# SCH.net
KiCad netlist of a schematic drawn in Altium Designer
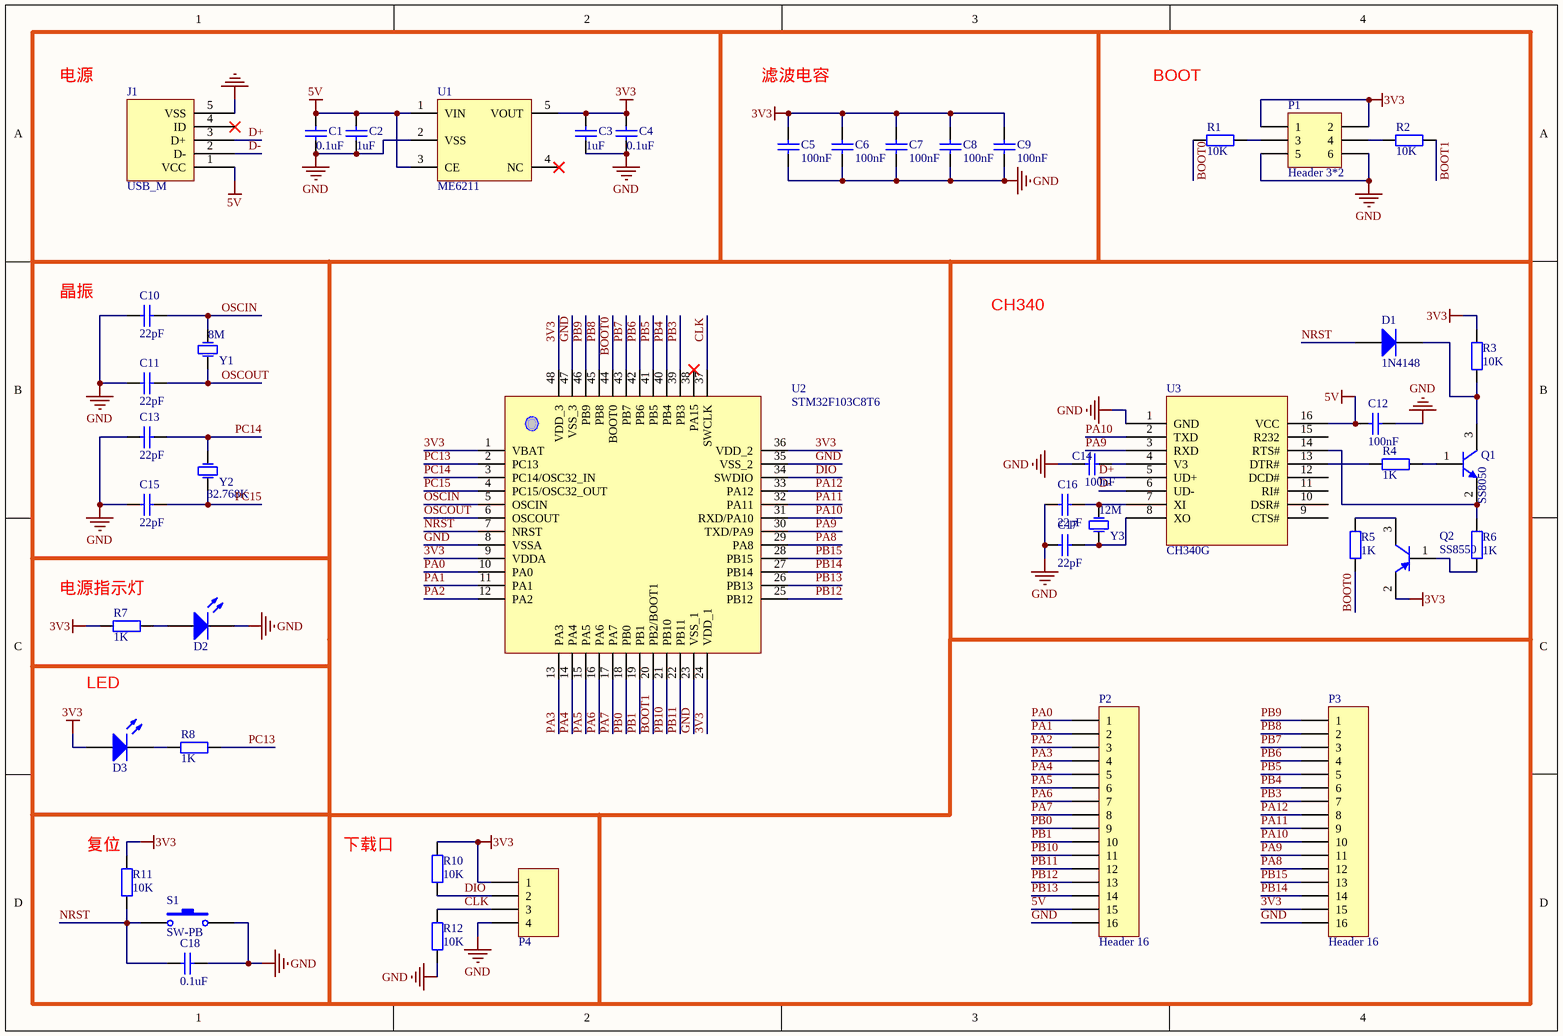
[diagram p0: SCH.SchDoc]

(export (version "E")
  (design (tool "Eeschema 10.0.6"))
  (components
    (comp (ref "C1")
      (value "0.1uF")
      (footprint "0603_C")
      (description "贴片电容")
      (fields (field (name "Comment") "Cap"))
      (libsource (lib "Miscellaneous Devices LC (1)") (part "0603 1uF (105) 10% 50V"))
    )
    (comp (ref "C2")
      (value "1uF")
      (footprint "0603_C")
      (description "贴片电容")
      (fields (field (name "Comment") "Cap"))
      (libsource (lib "Miscellaneous Devices LC (1)") (part "0603 1uF (105) 10% 50V"))
    )
    (comp (ref "C3")
      (value "1uF")
      (footprint "0603_C")
      (description "贴片电容")
      (fields (field (name "Comment") "Cap"))
      (libsource (lib "Miscellaneous Devices LC (1)") (part "0603 1uF (105) 10% 50V"))
    )
    (comp (ref "C4")
      (value "0.1uF")
      (footprint "0603_C")
      (description "贴片电容")
      (fields (field (name "Comment") "Cap"))
      (libsource (lib "Miscellaneous Devices LC (1)") (part "0603 1uF (105) 10% 50V"))
    )
    (comp (ref "C5")
      (value "100nF")
      (footprint "0603_C")
      (description "无极性电容")
      (fields (field (name "Comment") "Cap") (field (name "PUBLISHER") "Altium Limited"))
      (libsource (lib "fszhang") (part "Cap"))
    )
    (comp (ref "C6")
      (value "100nF")
      (footprint "0603_C")
      (description "无极性电容")
      (fields (field (name "Comment") "Cap") (field (name "PUBLISHER") "Altium Limited"))
      (libsource (lib "fszhang") (part "Cap"))
    )
    (comp (ref "C7")
      (value "100nF")
      (footprint "0603_C")
      (description "无极性电容")
      (fields (field (name "Comment") "Cap") (field (name "PUBLISHER") "Altium Limited"))
      (libsource (lib "fszhang") (part "Cap"))
    )
    (comp (ref "C8")
      (value "100nF")
      (footprint "0603_C")
      (description "无极性电容")
      (fields (field (name "Comment") "Cap") (field (name "PUBLISHER") "Altium Limited"))
      (libsource (lib "fszhang") (part "Cap"))
    )
    (comp (ref "C9")
      (value "100nF")
      (footprint "0603_C")
      (description "无极性电容")
      (fields (field (name "Comment") "Cap") (field (name "PUBLISHER") "Altium Limited"))
      (libsource (lib "fszhang") (part "Cap"))
    )
    (comp (ref "C10")
      (value "22pF")
      (footprint "0603_C")
      (description "无极性电容")
      (fields (field (name "Comment") "Cap") (field (name "PUBLISHER") "Altium Limited"))
      (libsource (lib "fszhang") (part "Cap"))
    )
    (comp (ref "C11")
      (value "22pF")
      (footprint "0603_C")
      (description "无极性电容")
      (fields (field (name "Comment") "Cap") (field (name "PUBLISHER") "Altium Limited"))
      (libsource (lib "fszhang") (part "Cap"))
    )
    (comp (ref "C12")
      (value "100nF")
      (footprint "0603_C")
      (description "无极性电容")
      (fields (field (name "Comment") "Cap") (field (name "PUBLISHER") "Altium Limited"))
      (libsource (lib "fszhang") (part "Cap"))
    )
    (comp (ref "C13")
      (value "22pF")
      (footprint "0603_C")
      (description "无极性电容")
      (fields (field (name "Comment") "Cap") (field (name "PUBLISHER") "Altium Limited"))
      (libsource (lib "fszhang") (part "Cap"))
    )
    (comp (ref "C14")
      (value "100nF")
      (footprint "0603_C")
      (description "无极性电容")
      (fields (field (name "Comment") "Cap") (field (name "PUBLISHER") "Altium Limited"))
      (libsource (lib "fszhang") (part "Cap"))
    )
    (comp (ref "C15")
      (value "22pF")
      (footprint "0603_C")
      (description "无极性电容")
      (fields (field (name "Comment") "Cap") (field (name "PUBLISHER") "Altium Limited"))
      (libsource (lib "fszhang") (part "Cap"))
    )
    (comp (ref "C16")
      (value "22pF")
      (footprint "0603_C")
      (description "无极性电容")
      (fields (field (name "Comment") "Cap") (field (name "PUBLISHER") "Altium Limited"))
      (libsource (lib "fszhang") (part "Cap"))
    )
    (comp (ref "C17")
      (value "22pF")
      (footprint "0603_C")
      (description "无极性电容")
      (fields (field (name "Comment") "Cap") (field (name "PUBLISHER") "Altium Limited"))
      (libsource (lib "fszhang") (part "Cap"))
    )
    (comp (ref "C18")
      (value "0.1uF")
      (footprint "0603_C")
      (description "贴片电容")
      (fields (field (name "Comment") "Cap"))
      (libsource (lib "Miscellaneous Devices LC (1)") (part "0603 1uF (105) 10% 50V"))
    )
    (comp (ref "D1")
      (value "Diode")
      (footprint "SOD-323")
      (description "二极管")
      (fields (field (name "TYPE") "1N4148") (field (name "PUBLISHER") "Altium Limited"))
      (libsource (lib "fszhang") (part "Diode"))
    )
    (comp (ref "D2")
      (value "LED0")
      (footprint "LED_0805_Blue")
      (description "发光二极管")
      (fields (field (name "PUBLISHER") "Altium Limited"))
      (libsource (lib "fszhang") (part "LED0"))
    )
    (comp (ref "D3")
      (value "LED0")
      (footprint "LED_0805_Blue")
      (description "发光二极管")
      (fields (field (name "PUBLISHER") "Altium Limited"))
      (libsource (lib "fszhang") (part "LED0"))
    )
    (comp (ref "J1")
      (value "USB_M")
      (footprint "USB")
      (description "MicroUSB接口")
      (libsource (lib "fszhang") (part "USB_M"))
    )
    (comp (ref "P1")
      (value "Header 3*2")
      (footprint "HDR3X2")
      (description "接插件")
      (libsource (lib "fszhang") (part "Header 3*2"))
    )
    (comp (ref "P2")
      (value "Header 16")
      (footprint "HDR16X1_A")
      (description "Header16贴片")
      (fields (field (name "PUBLISHER") "Altium Limited"))
      (libsource (lib "fszhang") (part "Header 16"))
    )
    (comp (ref "P3")
      (value "Header 16")
      (footprint "HDR16X1_A")
      (description "Header16贴片")
      (fields (field (name "PUBLISHER") "Altium Limited"))
      (libsource (lib "fszhang") (part "Header 16"))
    )
    (comp (ref "P4")
      (value "Header 4")
      (footprint "HDR4X1_A")
      (description "接插件")
      (fields (field (name "PUBLISHER") "Altium Limited"))
      (libsource (lib "fszhang") (part "Header 4"))
    )
    (comp (ref "Q1")
      (value "SS8050")
      (footprint "SOT-23")
      (description "NPN贴片三极管")
      (fields (field (name "PUBLISHER") "Altium Limited"))
      (libsource (lib "fszhang") (part "SS8050"))
    )
    (comp (ref "Q2")
      (value "SS8550")
      (footprint "SOT-23")
      (description "PNP贴片三极管")
      (fields (field (name "PUBLISHER") "Altium Limited"))
      (libsource (lib "fszhang") (part "SS8550"))
    )
    (comp (ref "R1")
      (value "10K")
      (footprint "0603_R")
      (description "贴片电阻")
      (fields (field (name "Comment") "Res1") (field (name "PUBLISHER") "Altium Limited"))
      (libsource (lib "") (part "Res1_2"))
    )
    (comp (ref "R2")
      (value "10K")
      (footprint "0603_R")
      (description "贴片电阻")
      (fields (field (name "Comment") "Res1") (field (name "PUBLISHER") "Altium Limited"))
      (libsource (lib "") (part "Res1_2"))
    )
    (comp (ref "R3")
      (value "10K")
      (footprint "0603_R")
      (description "贴片电阻")
      (fields (field (name "Comment") "Res1") (field (name "PUBLISHER") "Altium Limited"))
      (libsource (lib "") (part "Res1_1"))
    )
    (comp (ref "R4")
      (value "1K")
      (footprint "0603_R")
      (description "贴片电阻")
      (fields (field (name "Comment") "Res1") (field (name "PUBLISHER") "Altium Limited"))
      (libsource (lib "") (part "Res1_2"))
    )
    (comp (ref "R5")
      (value "1K")
      (footprint "0603_R")
      (description "贴片电阻")
      (fields (field (name "Comment") "Res1") (field (name "PUBLISHER") "Altium Limited"))
      (libsource (lib "") (part "Res1_1"))
    )
    (comp (ref "R6")
      (value "1K")
      (footprint "0603_R")
      (description "贴片电阻")
      (fields (field (name "Comment") "Res1") (field (name "PUBLISHER") "Altium Limited"))
      (libsource (lib "") (part "Res1_1"))
    )
    (comp (ref "R7")
      (value "1K")
      (footprint "0603_R")
      (description "贴片电阻")
      (fields (field (name "Comment") "Res1") (field (name "PUBLISHER") "Altium Limited"))
      (libsource (lib "fszhang") (part "Res1"))
    )
    (comp (ref "R8")
      (value "1K")
      (footprint "0603_R")
      (description "贴片电阻")
      (fields (field (name "Comment") "Res1") (field (name "PUBLISHER") "Altium Limited"))
      (libsource (lib "fszhang") (part "Res1"))
    )
    (comp (ref "R10")
      (value "10K")
      (footprint "0603_R")
      (description "贴片电阻")
      (fields (field (name "Comment") "Res1") (field (name "PUBLISHER") "Altium Limited"))
      (libsource (lib "") (part "Res1_3"))
    )
    (comp (ref "R11")
      (value "10K")
      (footprint "0603_R")
      (description "贴片电阻")
      (fields (field (name "Comment") "Res1") (field (name "PUBLISHER") "Altium Limited"))
      (libsource (lib "") (part "Res1_1"))
    )
    (comp (ref "R12")
      (value "10K")
      (footprint "0603_R")
      (description "贴片电阻")
      (fields (field (name "Comment") "Res1") (field (name "PUBLISHER") "Altium Limited"))
      (libsource (lib "") (part "Res1_3"))
    )
    (comp (ref "S1")
      (value "SW-PB")
      (footprint "SW_PB2_A1")
      (description "微动开关")
      (fields (field (name "PUBLISHER") "Altium Limited"))
      (libsource (lib "fszhang") (part "SW-PB"))
    )
    (comp (ref "U1") (value "ME6211") (footprint "SOT23-5") (libsource (lib "fszhang") (part "ME6211")))
    (comp (ref "U2")
      (value "STM32F103C8T6")
      (footprint "LQFP-48_M")
      (description "STM32单片机48引脚")
      (libsource (lib "fszhang") (part "STM32F103C8T6"))
    )
    (comp (ref "U3")
      (value "CH340G")
      (footprint "SOP-16")
      (description "串口芯片")
      (libsource (lib "fszhang") (part "CH340G"))
    )
    (comp (ref "Y1")
      (value "8M")
      (footprint "5032")
      (description "晶振")
      (fields (field (name "PUBLISHER") "Altium Limited"))
      (libsource (lib "fszhang") (part "XTAL"))
    )
    (comp (ref "Y2")
      (value "32.768K")
      (footprint "3215")
      (description "晶振")
      (fields (field (name "PUBLISHER") "Altium Limited"))
      (libsource (lib "fszhang") (part "XTAL"))
    )
    (comp (ref "Y3")
      (value "12M")
      (footprint "5032")
      (description "晶振")
      (fields (field (name "PUBLISHER") "Altium Limited"))
      (libsource (lib "fszhang") (part "XTAL"))
    )
  )
  (nets
    (net (code "1") (name "/BOOT0") (class "Default")
      (node (ref "R1") (pin "1") (pinfunction "1_1") (pintype "passive"))
      (node (ref "R5") (pin "1") (pinfunction "1_1") (pintype "passive"))
      (node (ref "U2") (pin "44") (pinfunction "BOOT0_44") (pintype "passive"))
    )
    (net (code "2") (name "/BOOT1") (class "Default")
      (node (ref "R2") (pin "2") (pinfunction "2_2") (pintype "passive"))
      (node (ref "U2") (pin "20") (pinfunction "PB2/BOOT1_20") (pintype "passive"))
    )
    (net (code "3") (name "/CLK") (class "Default")
      (node (ref "P4") (pin "3") (pinfunction "3_3") (pintype "passive"))
      (node (ref "R12") (pin "1") (pinfunction "1_1") (pintype "passive"))
      (node (ref "U2") (pin "37") (pinfunction "SWCLK_37") (pintype "passive"))
    )
    (net (code "4") (name "/D+") (class "Default")
      (node (ref "J1") (pin "3") (pinfunction "D+_3") (pintype "passive"))
      (node (ref "U3") (pin "5") (pinfunction "UD+_5") (pintype "passive"))
    )
    (net (code "5") (name "/D-") (class "Default")
      (node (ref "J1") (pin "2") (pinfunction "D-_2") (pintype "passive"))
      (node (ref "U3") (pin "6") (pinfunction "UD-_6") (pintype "passive"))
    )
    (net (code "6") (name "/DIO") (class "Default")
      (node (ref "P4") (pin "2") (pinfunction "2_2") (pintype "passive"))
      (node (ref "R10") (pin "2") (pinfunction "2_2") (pintype "passive"))
      (node (ref "U2") (pin "34") (pinfunction "SWDIO_34") (pintype "passive"))
    )
    (net (code "7") (name "/NRST") (class "Default")
      (node (ref "C18") (pin "2") (pinfunction "2_2") (pintype "passive"))
      (node (ref "D1") (pin "1") (pinfunction "A_1") (pintype "passive"))
      (node (ref "R11") (pin "1") (pinfunction "1_1") (pintype "passive"))
      (node (ref "S1") (pin "1") (pinfunction "1_1") (pintype "passive"))
      (node (ref "U2") (pin "7") (pinfunction "NRST_7") (pintype "passive"))
    )
    (net (code "8") (name "/OSCIN") (class "Default")
      (node (ref "C10") (pin "2") (pinfunction "2_2") (pintype "passive"))
      (node (ref "U2") (pin "5") (pinfunction "OSCIN_5") (pintype "passive"))
      (node (ref "Y1") (pin "1") (pinfunction "OSC1_1") (pintype "passive"))
    )
    (net (code "9") (name "/OSCOUT") (class "Default")
      (node (ref "C11") (pin "2") (pinfunction "2_2") (pintype "passive"))
      (node (ref "U2") (pin "6") (pinfunction "OSCOUT_6") (pintype "passive"))
      (node (ref "Y1") (pin "2") (pinfunction "OSC2_2") (pintype "passive"))
    )
    (net (code "10") (name "/PA0") (class "Default")
      (node (ref "P2") (pin "1") (pinfunction "1_1") (pintype "passive"))
      (node (ref "U2") (pin "10") (pinfunction "PA0_10") (pintype "passive"))
    )
    (net (code "11") (name "/PA1") (class "Default")
      (node (ref "P2") (pin "2") (pinfunction "2_2") (pintype "passive"))
      (node (ref "U2") (pin "11") (pinfunction "PA1_11") (pintype "passive"))
    )
    (net (code "12") (name "/PA2") (class "Default")
      (node (ref "P2") (pin "3") (pinfunction "3_3") (pintype "passive"))
      (node (ref "U2") (pin "12") (pinfunction "PA2_12") (pintype "passive"))
    )
    (net (code "13") (name "/PA3") (class "Default")
      (node (ref "P2") (pin "4") (pinfunction "4_4") (pintype "passive"))
      (node (ref "U2") (pin "13") (pinfunction "PA3_13") (pintype "passive"))
    )
    (net (code "14") (name "/PA4") (class "Default")
      (node (ref "P2") (pin "5") (pinfunction "5_5") (pintype "passive"))
      (node (ref "U2") (pin "14") (pinfunction "PA4_14") (pintype "passive"))
    )
    (net (code "15") (name "/PA5") (class "Default")
      (node (ref "P2") (pin "6") (pinfunction "6_6") (pintype "passive"))
      (node (ref "U2") (pin "15") (pinfunction "PA5_15") (pintype "passive"))
    )
    (net (code "16") (name "/PA6") (class "Default")
      (node (ref "P2") (pin "7") (pinfunction "7_7") (pintype "passive"))
      (node (ref "U2") (pin "16") (pinfunction "PA6_16") (pintype "passive"))
    )
    (net (code "17") (name "/PA7") (class "Default")
      (node (ref "P2") (pin "8") (pinfunction "8_8") (pintype "passive"))
      (node (ref "U2") (pin "17") (pinfunction "PA7_17") (pintype "passive"))
    )
    (net (code "18") (name "/PA8") (class "Default")
      (node (ref "P3") (pin "12") (pinfunction "12_12") (pintype "passive"))
      (node (ref "U2") (pin "29") (pinfunction "PA8_29") (pintype "passive"))
    )
    (net (code "19") (name "/PA9") (class "Default")
      (node (ref "P3") (pin "11") (pinfunction "11_11") (pintype "passive"))
      (node (ref "U2") (pin "30") (pinfunction "TXD/PA9_30") (pintype "passive"))
      (node (ref "U3") (pin "3") (pinfunction "RXD_3") (pintype "passive"))
    )
    (net (code "20") (name "/PA10") (class "Default")
      (node (ref "P3") (pin "10") (pinfunction "10_10") (pintype "passive"))
      (node (ref "U2") (pin "31") (pinfunction "RXD/PA10_31") (pintype "passive"))
      (node (ref "U3") (pin "2") (pinfunction "TXD_2") (pintype "passive"))
    )
    (net (code "21") (name "/PA11") (class "Default")
      (node (ref "P3") (pin "9") (pinfunction "9_9") (pintype "passive"))
      (node (ref "U2") (pin "32") (pinfunction "PA11_32") (pintype "passive"))
    )
    (net (code "22") (name "/PA12") (class "Default")
      (node (ref "P3") (pin "8") (pinfunction "8_8") (pintype "passive"))
      (node (ref "U2") (pin "33") (pinfunction "PA12_33") (pintype "passive"))
    )
    (net (code "23") (name "/PB0") (class "Default")
      (node (ref "P2") (pin "9") (pinfunction "9_9") (pintype "passive"))
      (node (ref "U2") (pin "18") (pinfunction "PB0_18") (pintype "passive"))
    )
    (net (code "24") (name "/PB1") (class "Default")
      (node (ref "P2") (pin "10") (pinfunction "10_10") (pintype "passive"))
      (node (ref "U2") (pin "19") (pinfunction "PB1_19") (pintype "passive"))
    )
    (net (code "25") (name "/PB3") (class "Default")
      (node (ref "P3") (pin "7") (pinfunction "7_7") (pintype "passive"))
      (node (ref "U2") (pin "39") (pinfunction "PB3_39") (pintype "passive"))
    )
    (net (code "26") (name "/PB4") (class "Default")
      (node (ref "P3") (pin "6") (pinfunction "6_6") (pintype "passive"))
      (node (ref "U2") (pin "40") (pinfunction "PB4_40") (pintype "passive"))
    )
    (net (code "27") (name "/PB5") (class "Default")
      (node (ref "P3") (pin "5") (pinfunction "5_5") (pintype "passive"))
      (node (ref "U2") (pin "41") (pinfunction "PB5_41") (pintype "passive"))
    )
    (net (code "28") (name "/PB6") (class "Default")
      (node (ref "P3") (pin "4") (pinfunction "4_4") (pintype "passive"))
      (node (ref "U2") (pin "42") (pinfunction "PB6_42") (pintype "passive"))
    )
    (net (code "29") (name "/PB7") (class "Default")
      (node (ref "P3") (pin "3") (pinfunction "3_3") (pintype "passive"))
      (node (ref "U2") (pin "43") (pinfunction "PB7_43") (pintype "passive"))
    )
    (net (code "30") (name "/PB8") (class "Default")
      (node (ref "P3") (pin "2") (pinfunction "2_2") (pintype "passive"))
      (node (ref "U2") (pin "45") (pinfunction "PB8_45") (pintype "passive"))
    )
    (net (code "31") (name "/PB9") (class "Default")
      (node (ref "P3") (pin "1") (pinfunction "1_1") (pintype "passive"))
      (node (ref "U2") (pin "46") (pinfunction "PB9_46") (pintype "passive"))
    )
    (net (code "32") (name "/PB10") (class "Default")
      (node (ref "P2") (pin "11") (pinfunction "11_11") (pintype "passive"))
      (node (ref "U2") (pin "21") (pinfunction "PB10_21") (pintype "passive"))
    )
    (net (code "33") (name "/PB11") (class "Default")
      (node (ref "P2") (pin "12") (pinfunction "12_12") (pintype "passive"))
      (node (ref "U2") (pin "22") (pinfunction "PB11_22") (pintype "passive"))
    )
    (net (code "34") (name "/PB12") (class "Default")
      (node (ref "P2") (pin "13") (pinfunction "13_13") (pintype "passive"))
      (node (ref "U2") (pin "25") (pinfunction "PB12_25") (pintype "passive"))
    )
    (net (code "35") (name "/PB13") (class "Default")
      (node (ref "P2") (pin "14") (pinfunction "14_14") (pintype "passive"))
      (node (ref "U2") (pin "26") (pinfunction "PB13_26") (pintype "passive"))
    )
    (net (code "36") (name "/PB14") (class "Default")
      (node (ref "P3") (pin "14") (pinfunction "14_14") (pintype "passive"))
      (node (ref "U2") (pin "27") (pinfunction "PB14_27") (pintype "passive"))
    )
    (net (code "37") (name "/PB15") (class "Default")
      (node (ref "P3") (pin "13") (pinfunction "13_13") (pintype "passive"))
      (node (ref "U2") (pin "28") (pinfunction "PB15_28") (pintype "passive"))
    )
    (net (code "38") (name "/PC13") (class "Default")
      (node (ref "R8") (pin "1") (pinfunction "1_1") (pintype "passive"))
      (node (ref "U2") (pin "2") (pinfunction "PC13_2") (pintype "passive"))
    )
    (net (code "39") (name "/PC14") (class "Default")
      (node (ref "C13") (pin "2") (pinfunction "2_2") (pintype "passive"))
      (node (ref "U2") (pin "3") (pinfunction "PC14/OSC32_IN_3") (pintype "passive"))
      (node (ref "Y2") (pin "1") (pinfunction "OSC1_1") (pintype "passive"))
    )
    (net (code "40") (name "/PC15") (class "Default")
      (node (ref "C15") (pin "2") (pinfunction "2_2") (pintype "passive"))
      (node (ref "U2") (pin "4") (pinfunction "PC15/OSC32_OUT_4") (pintype "passive"))
      (node (ref "Y2") (pin "2") (pinfunction "OSC2_2") (pintype "passive"))
    )
    (net (code "41") (name "3V3") (class "Default")
      (node (ref "C3") (pin "2") (pinfunction "2_2") (pintype "passive"))
      (node (ref "C4") (pin "2") (pinfunction "2_2") (pintype "passive"))
      (node (ref "C5") (pin "2") (pinfunction "2_2") (pintype "passive"))
      (node (ref "C6") (pin "2") (pinfunction "2_2") (pintype "passive"))
      (node (ref "C7") (pin "2") (pinfunction "2_2") (pintype "passive"))
      (node (ref "C8") (pin "2") (pinfunction "2_2") (pintype "passive"))
      (node (ref "C9") (pin "2") (pinfunction "2_2") (pintype "passive"))
      (node (ref "D3") (pin "1") (pinfunction "A_1") (pintype "passive"))
      (node (ref "P1") (pin "1") (pinfunction "1_1") (pintype "passive"))
      (node (ref "P1") (pin "2") (pinfunction "2_2") (pintype "passive"))
      (node (ref "P3") (pin "15") (pinfunction "15_15") (pintype "passive"))
      (node (ref "P4") (pin "1") (pinfunction "1_1") (pintype "passive"))
      (node (ref "Q2") (pin "2") (pinfunction "E_2") (pintype "passive"))
      (node (ref "R10") (pin "1") (pinfunction "1_1") (pintype "passive"))
      (node (ref "R11") (pin "2") (pinfunction "2_2") (pintype "passive"))
      (node (ref "R3") (pin "2") (pinfunction "2_2") (pintype "passive"))
      (node (ref "R7") (pin "2") (pinfunction "2_2") (pintype "passive"))
      (node (ref "U1") (pin "5") (pinfunction "VOUT_5") (pintype "passive"))
      (node (ref "U2") (pin "1") (pinfunction "VBAT_1") (pintype "passive"))
      (node (ref "U2") (pin "24") (pinfunction "VDD_1_24") (pintype "passive"))
      (node (ref "U2") (pin "36") (pinfunction "VDD_2_36") (pintype "passive"))
      (node (ref "U2") (pin "48") (pinfunction "VDD_3_48") (pintype "passive"))
      (node (ref "U2") (pin "9") (pinfunction "VDDA_9") (pintype "passive"))
    )
    (net (code "42") (name "5V") (class "Default")
      (node (ref "C1") (pin "2") (pinfunction "2_2") (pintype "passive"))
      (node (ref "C12") (pin "2") (pinfunction "2_2") (pintype "passive"))
      (node (ref "C2") (pin "2") (pinfunction "2_2") (pintype "passive"))
      (node (ref "J1") (pin "1") (pinfunction "VCC_1") (pintype "passive"))
      (node (ref "P2") (pin "15") (pinfunction "15_15") (pintype "passive"))
      (node (ref "U1") (pin "1") (pinfunction "VIN_1") (pintype "passive"))
      (node (ref "U1") (pin "3") (pinfunction "CE_3") (pintype "passive"))
      (node (ref "U3") (pin "16") (pinfunction "VCC_16") (pintype "power_in"))
    )
    (net (code "43") (name "GND") (class "Default")
      (node (ref "C1") (pin "1") (pinfunction "1_1") (pintype "passive"))
      (node (ref "C10") (pin "1") (pinfunction "1_1") (pintype "passive"))
      (node (ref "C11") (pin "1") (pinfunction "1_1") (pintype "passive"))
      (node (ref "C12") (pin "1") (pinfunction "1_1") (pintype "passive"))
      (node (ref "C13") (pin "1") (pinfunction "1_1") (pintype "passive"))
      (node (ref "C14") (pin "2") (pinfunction "2_2") (pintype "passive"))
      (node (ref "C15") (pin "1") (pinfunction "1_1") (pintype "passive"))
      (node (ref "C16") (pin "1") (pinfunction "1_1") (pintype "passive"))
      (node (ref "C17") (pin "1") (pinfunction "1_1") (pintype "passive"))
      (node (ref "C18") (pin "1") (pinfunction "1_1") (pintype "passive"))
      (node (ref "C2") (pin "1") (pinfunction "1_1") (pintype "passive"))
      (node (ref "C3") (pin "1") (pinfunction "1_1") (pintype "passive"))
      (node (ref "C4") (pin "1") (pinfunction "1_1") (pintype "passive"))
      (node (ref "C5") (pin "1") (pinfunction "1_1") (pintype "passive"))
      (node (ref "C6") (pin "1") (pinfunction "1_1") (pintype "passive"))
      (node (ref "C7") (pin "1") (pinfunction "1_1") (pintype "passive"))
      (node (ref "C8") (pin "1") (pinfunction "1_1") (pintype "passive"))
      (node (ref "C9") (pin "1") (pinfunction "1_1") (pintype "passive"))
      (node (ref "D2") (pin "2") (pinfunction "K_2") (pintype "passive"))
      (node (ref "J1") (pin "5") (pinfunction "VSS_5") (pintype "passive"))
      (node (ref "P1") (pin "5") (pinfunction "5_5") (pintype "passive"))
      (node (ref "P1") (pin "6") (pinfunction "6_6") (pintype "passive"))
      (node (ref "P2") (pin "16") (pinfunction "16_16") (pintype "passive"))
      (node (ref "P3") (pin "16") (pinfunction "16_16") (pintype "passive"))
      (node (ref "P4") (pin "4") (pinfunction "4_4") (pintype "passive"))
      (node (ref "R12") (pin "2") (pinfunction "2_2") (pintype "passive"))
      (node (ref "S1") (pin "2") (pinfunction "2_2") (pintype "passive"))
      (node (ref "U1") (pin "2") (pinfunction "VSS_2") (pintype "passive"))
      (node (ref "U2") (pin "23") (pinfunction "VSS_1_23") (pintype "passive"))
      (node (ref "U2") (pin "35") (pinfunction "VSS_2_35") (pintype "passive"))
      (node (ref "U2") (pin "47") (pinfunction "VSS_3_47") (pintype "passive"))
      (node (ref "U2") (pin "8") (pinfunction "VSSA_8") (pintype "passive"))
      (node (ref "U3") (pin "1") (pinfunction "GND_1") (pintype "power_in"))
    )
    (net (code "44") (name "Net-(D1-K)") (class "Default")
      (node (ref "D1") (pin "2") (pinfunction "K_2") (pintype "passive"))
      (node (ref "Q1") (pin "3") (pinfunction "C_3") (pintype "passive"))
      (node (ref "R3") (pin "1") (pinfunction "1_1") (pintype "passive"))
    )
    (net (code "45") (name "Net-(D2-A)") (class "Default")
      (node (ref "D2") (pin "1") (pinfunction "A_1") (pintype "passive"))
      (node (ref "R7") (pin "1") (pinfunction "1_1") (pintype "passive"))
    )
    (net (code "46") (name "Net-(D3-K)") (class "Default")
      (node (ref "D3") (pin "2") (pinfunction "K_2") (pintype "passive"))
      (node (ref "R8") (pin "2") (pinfunction "2_2") (pintype "passive"))
    )
    (net (code "47") (name "Net-(P1-Pad3)") (class "Default")
      (node (ref "P1") (pin "3") (pinfunction "3_3") (pintype "passive"))
      (node (ref "R1") (pin "2") (pinfunction "2_2") (pintype "passive"))
    )
    (net (code "48") (name "Net-(P1-Pad4)") (class "Default")
      (node (ref "P1") (pin "4") (pinfunction "4_4") (pintype "passive"))
      (node (ref "R2") (pin "1") (pinfunction "1_1") (pintype "passive"))
    )
    (net (code "49") (name "Net-(Q1-B)") (class "Default")
      (node (ref "Q1") (pin "1") (pinfunction "B_1") (pintype "passive"))
      (node (ref "R4") (pin "2") (pinfunction "2_2") (pintype "passive"))
    )
    (net (code "50") (name "Net-(Q1-E)") (class "Default")
      (node (ref "Q1") (pin "2") (pinfunction "E_2") (pintype "passive"))
      (node (ref "R6") (pin "2") (pinfunction "2_2") (pintype "passive"))
      (node (ref "U3") (pin "14") (pinfunction "RTS#_14") (pintype "passive"))
    )
    (net (code "51") (name "Net-(Q2-B)") (class "Default")
      (node (ref "Q2") (pin "1") (pinfunction "B_1") (pintype "passive"))
      (node (ref "R6") (pin "1") (pinfunction "1_1") (pintype "passive"))
    )
    (net (code "52") (name "Net-(Q2-C)") (class "Default")
      (node (ref "Q2") (pin "3") (pinfunction "C_3") (pintype "passive"))
      (node (ref "R5") (pin "2") (pinfunction "2_2") (pintype "passive"))
    )
    (net (code "53") (name "Net-(U3-DTR#)") (class "Default")
      (node (ref "R4") (pin "1") (pinfunction "1_1") (pintype "passive"))
      (node (ref "U3") (pin "13") (pinfunction "DTR#_13") (pintype "passive"))
    )
    (net (code "54") (name "Net-(U3-V3)") (class "Default")
      (node (ref "C14") (pin "1") (pinfunction "1_1") (pintype "passive"))
      (node (ref "U3") (pin "4") (pinfunction "V3_4") (pintype "power_in"))
    )
    (net (code "55") (name "Net-(U3-XI)") (class "Default")
      (node (ref "C16") (pin "2") (pinfunction "2_2") (pintype "passive"))
      (node (ref "U3") (pin "7") (pinfunction "XI_7") (pintype "passive"))
      (node (ref "Y3") (pin "1") (pinfunction "OSC1_1") (pintype "passive"))
    )
    (net (code "56") (name "Net-(U3-XO)") (class "Default")
      (node (ref "C17") (pin "2") (pinfunction "2_2") (pintype "passive"))
      (node (ref "U3") (pin "8") (pinfunction "XO_8") (pintype "passive"))
      (node (ref "Y3") (pin "2") (pinfunction "OSC2_2") (pintype "passive"))
    )
    (net (code "57") (name "unconnected-(J1-ID-Pad4)") (class "Default")
      (node (ref "J1") (pin "4") (pinfunction "ID_4") (pintype "passive+no_connect"))
    )
    (net (code "58") (name "unconnected-(U1-NC-Pad4)") (class "Default")
      (node (ref "U1") (pin "4") (pinfunction "NC_4") (pintype "passive+no_connect"))
    )
    (net (code "59") (name "unconnected-(U2-PA15-Pad38)") (class "Default")
      (node (ref "U2") (pin "38") (pinfunction "PA15_38") (pintype "passive+no_connect"))
    )
    (net (code "60") (name "unconnected-(U3-CTS#-Pad9)") (class "Default")
      (node (ref "U3") (pin "9") (pinfunction "CTS#_9") (pintype "passive"))
    )
    (net (code "61") (name "unconnected-(U3-DCD#-Pad12)") (class "Default")
      (node (ref "U3") (pin "12") (pinfunction "DCD#_12") (pintype "passive"))
    )
    (net (code "62") (name "unconnected-(U3-DSR#-Pad10)") (class "Default")
      (node (ref "U3") (pin "10") (pinfunction "DSR#_10") (pintype "passive"))
    )
    (net (code "63") (name "unconnected-(U3-R232-Pad15)") (class "Default")
      (node (ref "U3") (pin "15") (pinfunction "R232_15") (pintype "passive"))
    )
    (net (code "64") (name "unconnected-(U3-RI#-Pad11)") (class "Default")
      (node (ref "U3") (pin "11") (pinfunction "RI#_11") (pintype "passive"))
    )
  )
)
